# dc-dc_eth_pump.net
KiCad netlist of a schematic drawn in Altium Designer
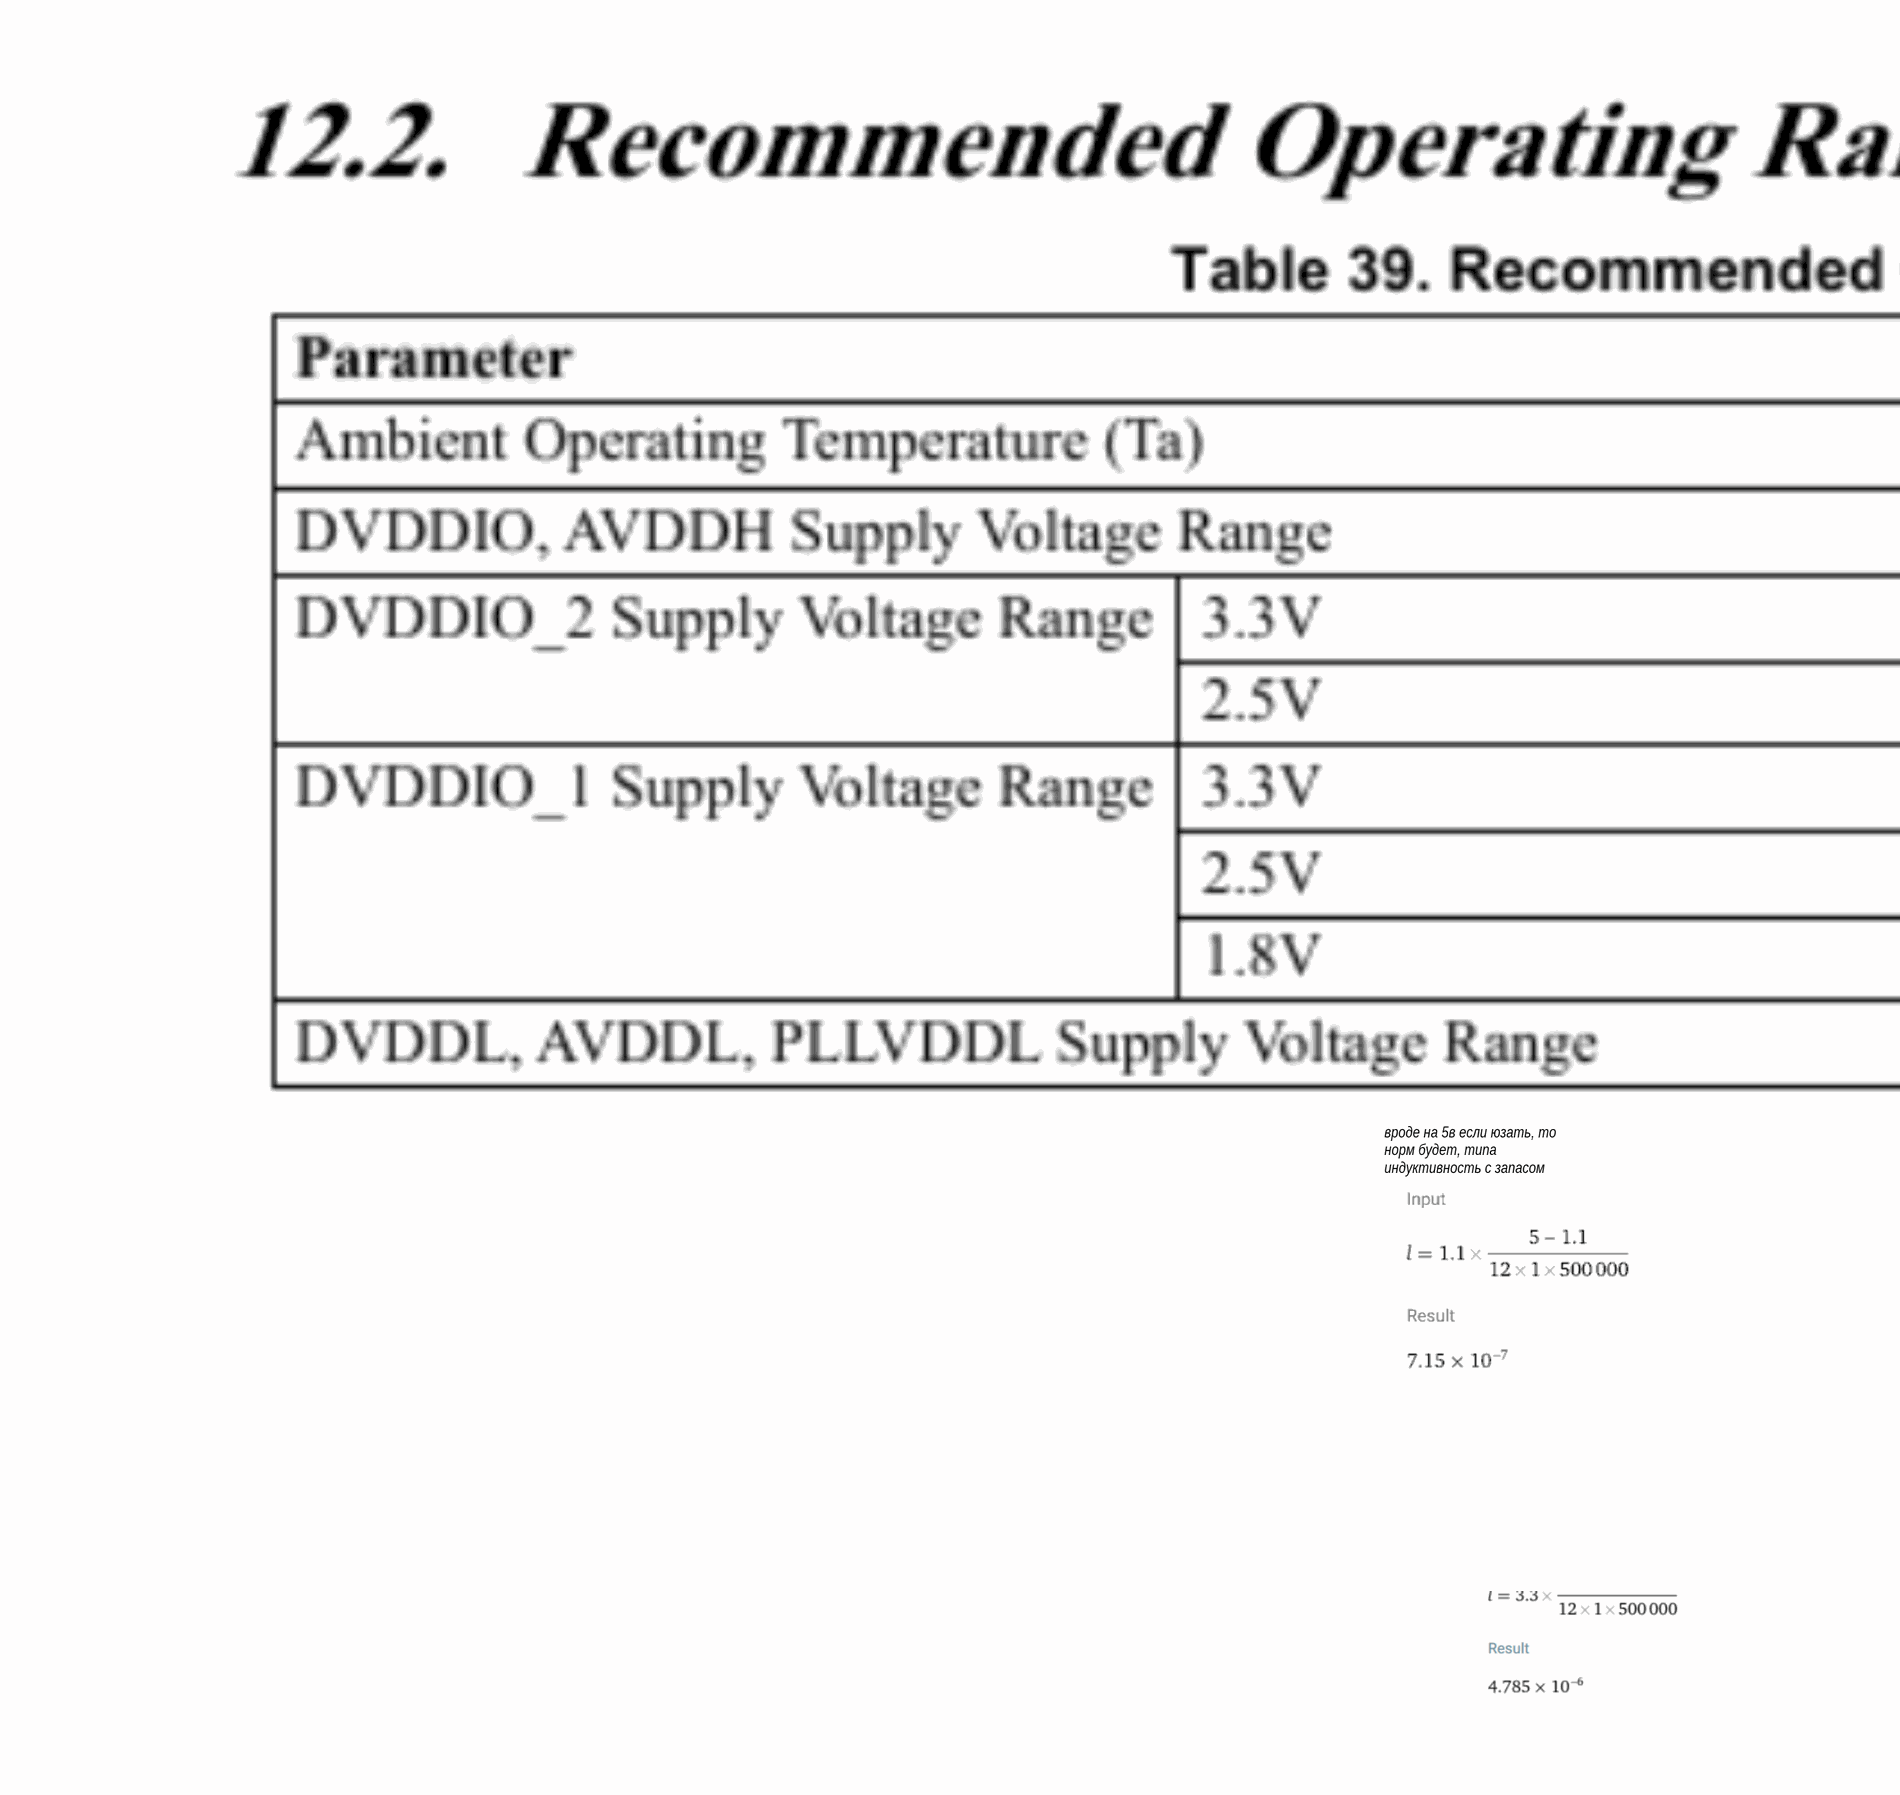
[diagram p0: dc-dc_eth+pump.SchDoc, top left]
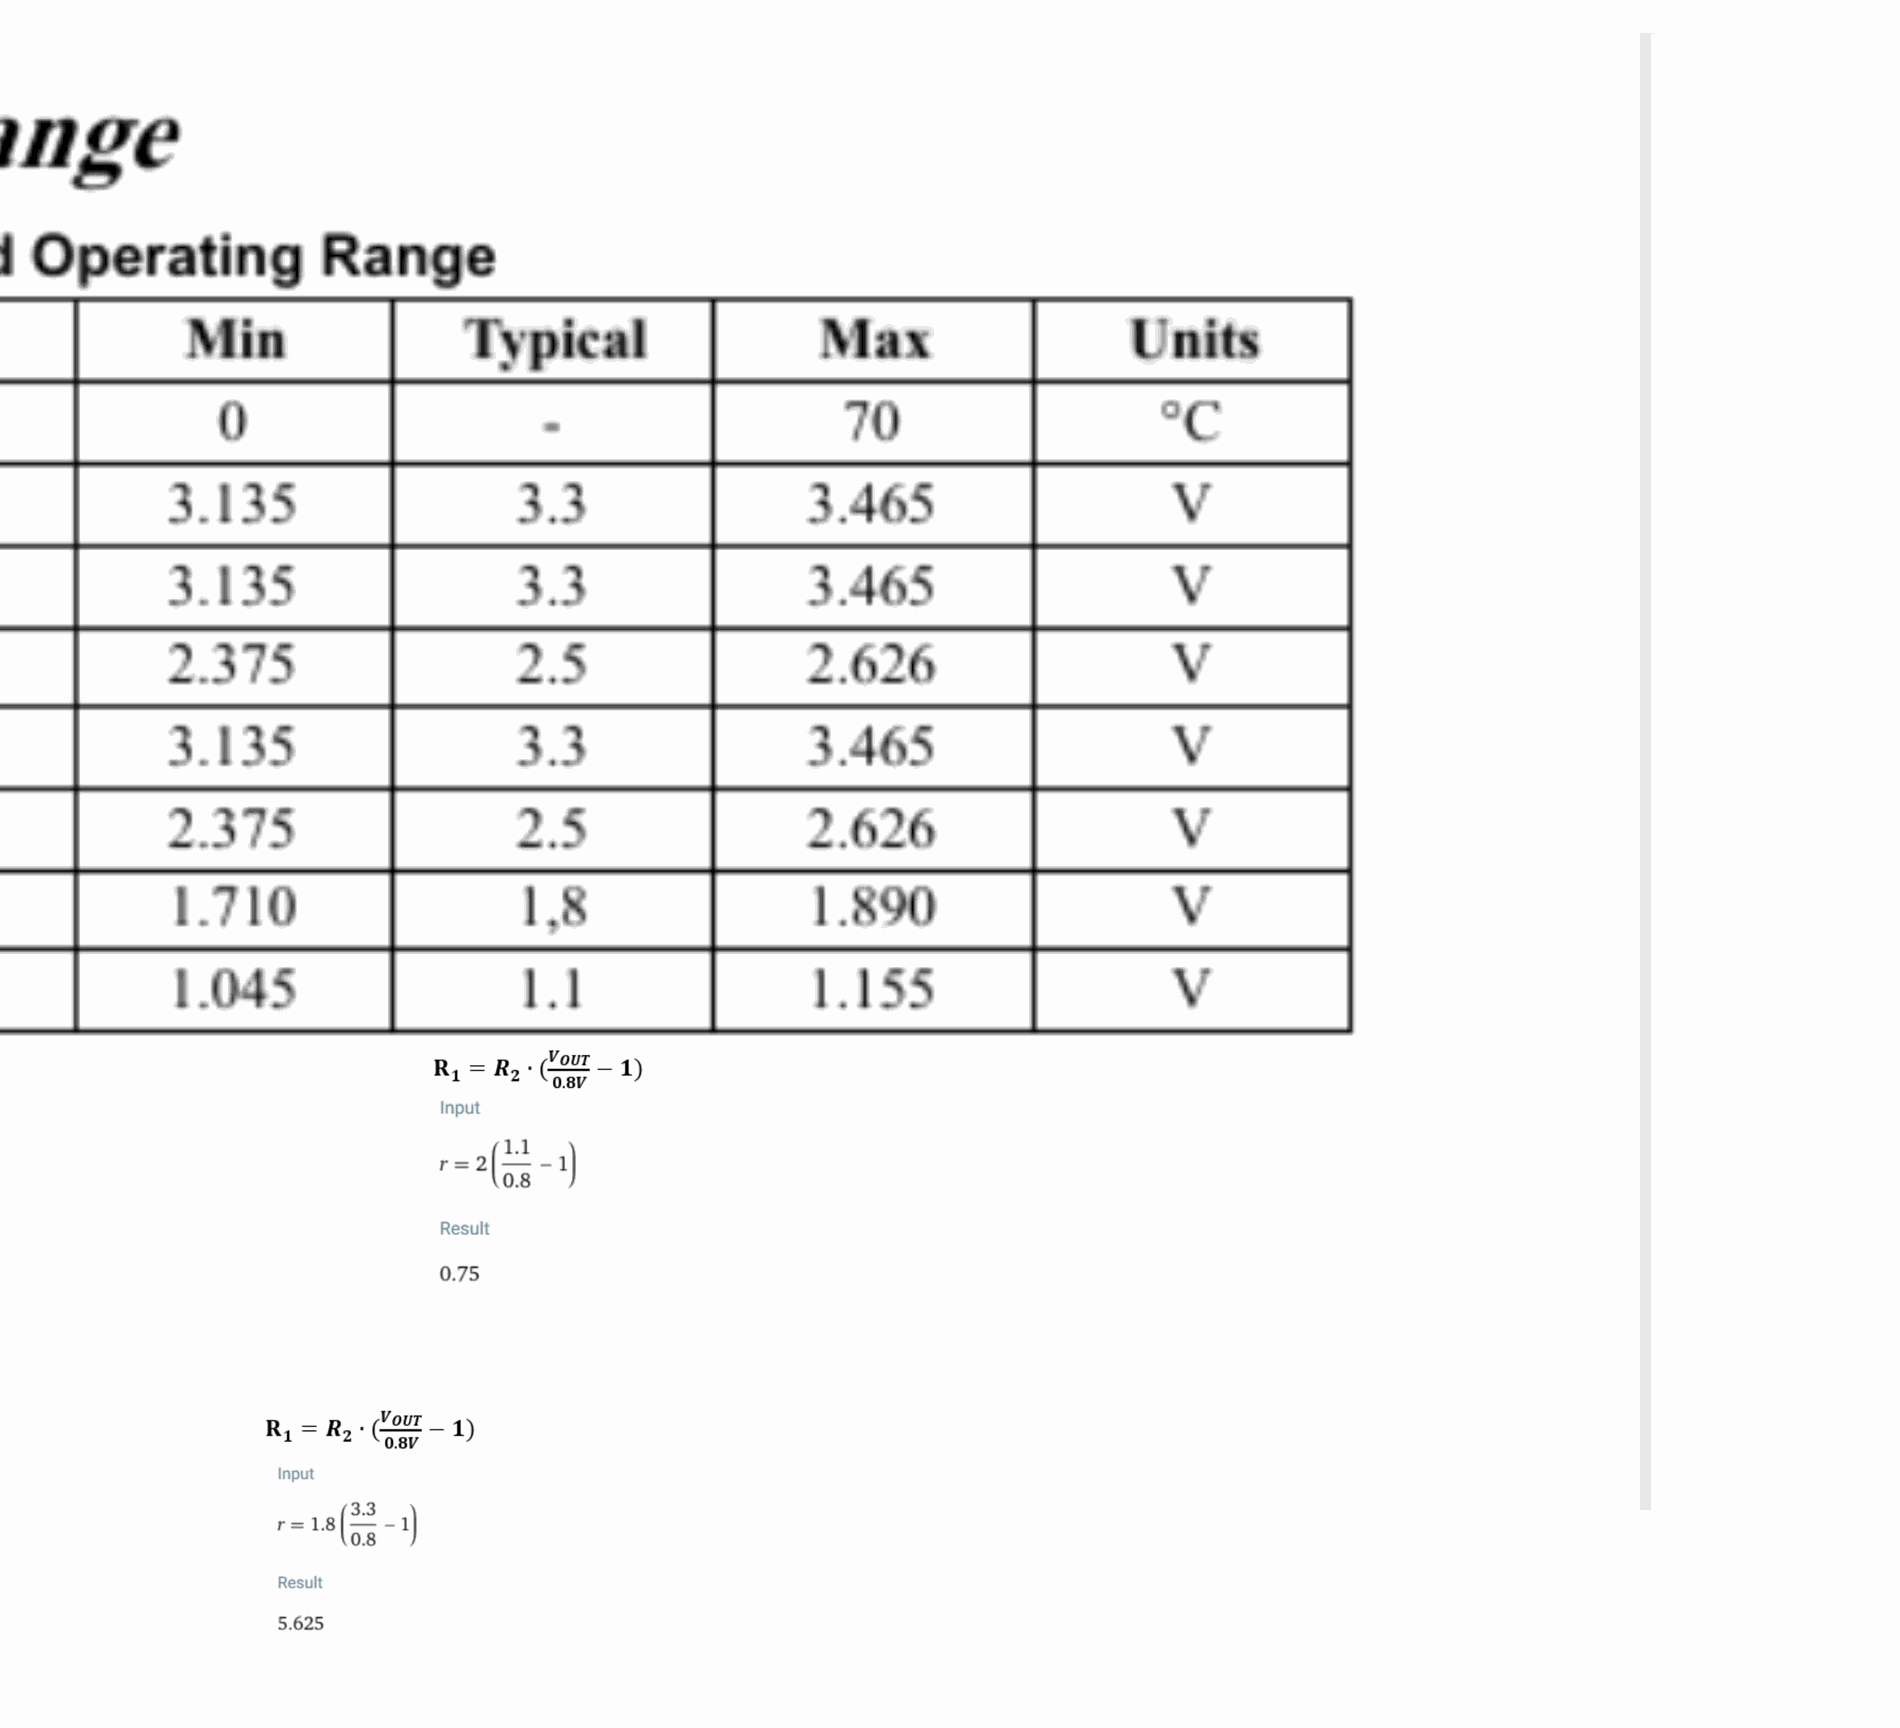
[diagram p1: dc-dc_eth+pump.SchDoc, top right]
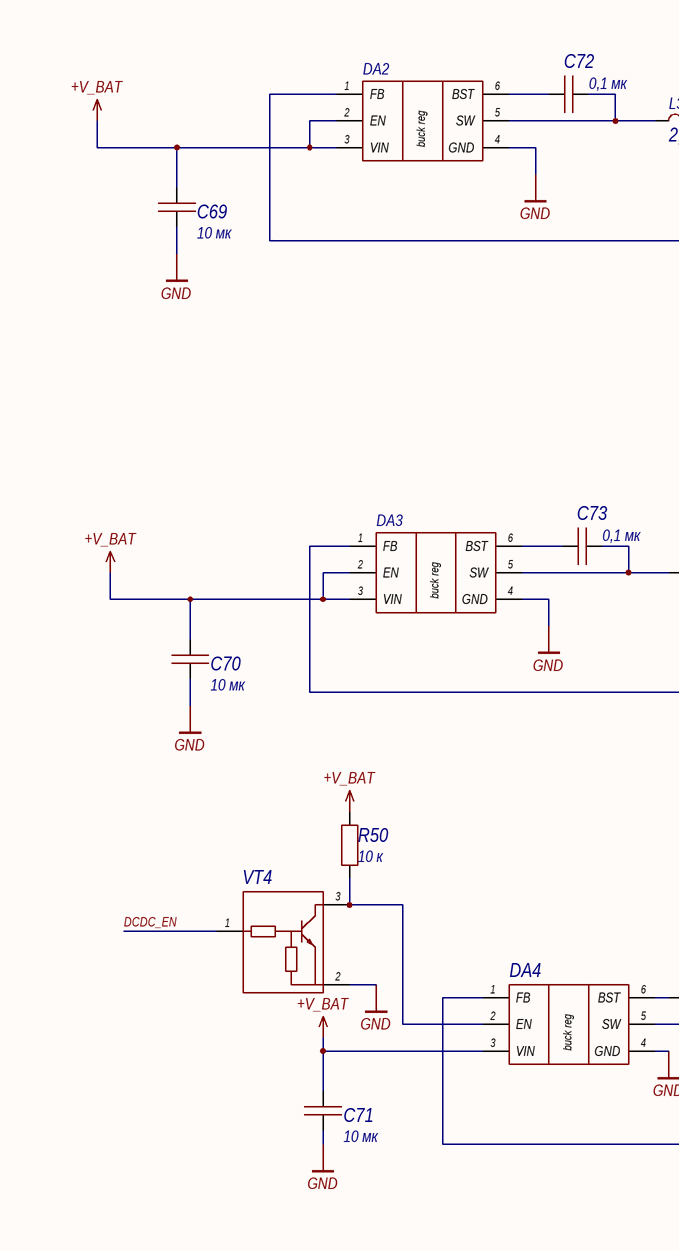
[diagram p2: dc-dc_eth+pump.SchDoc, bottom left]
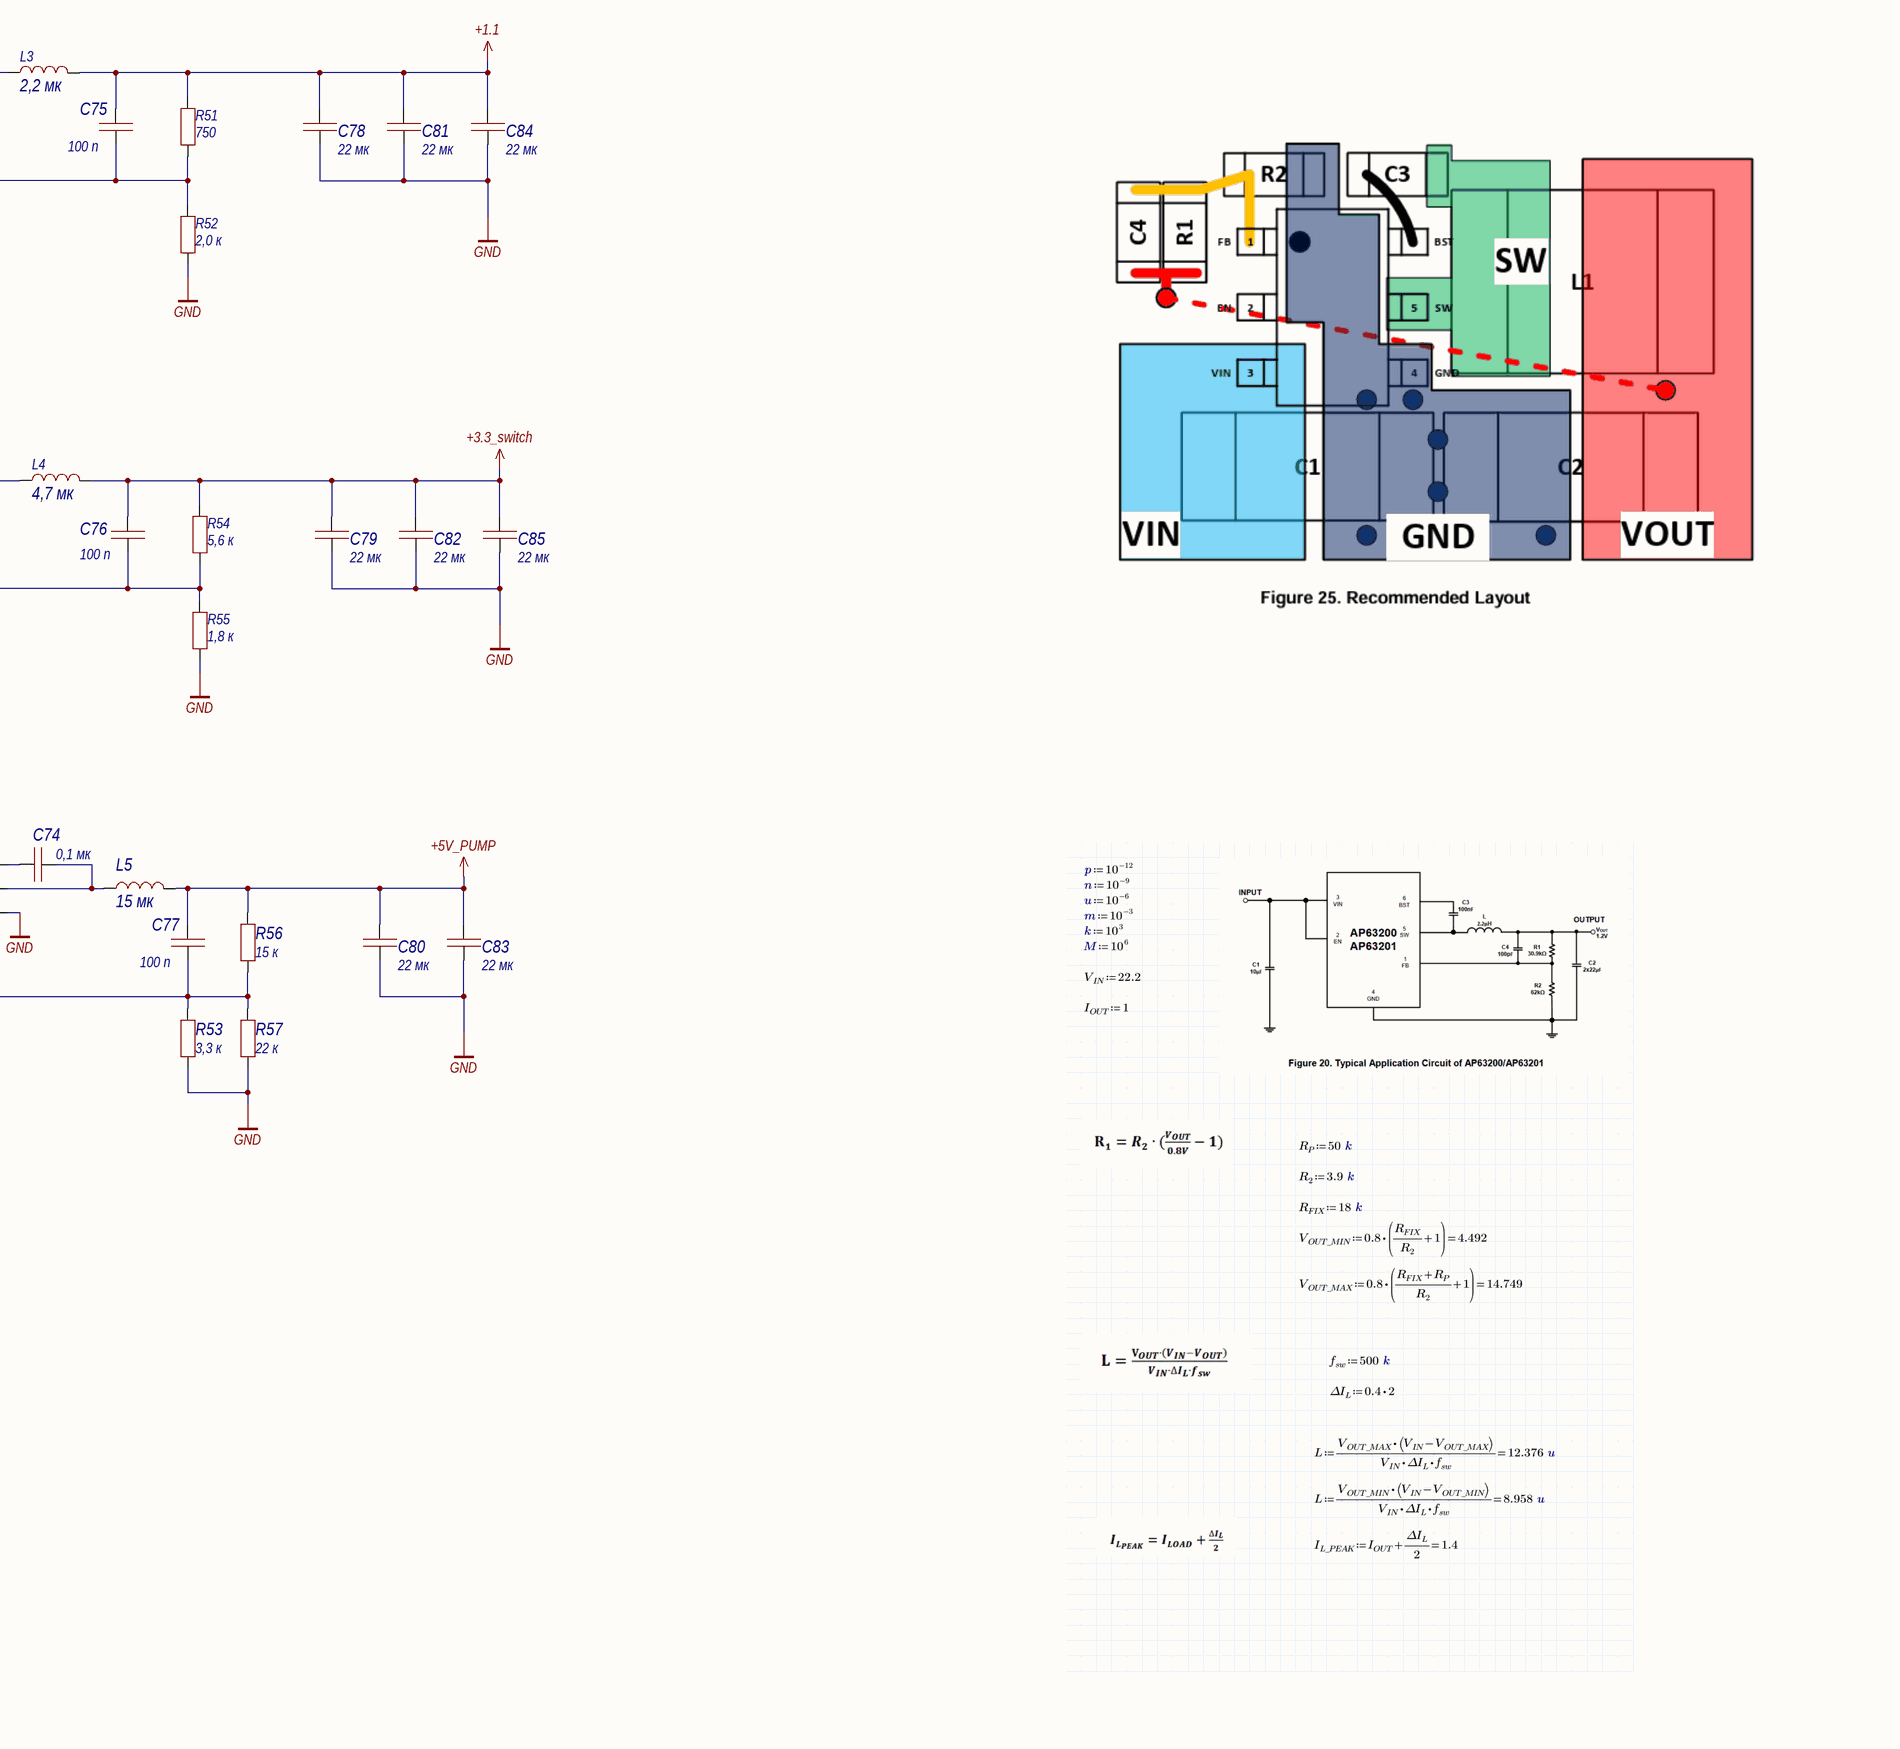
[diagram p3: dc-dc_eth+pump.SchDoc, bottom right]

(export (version "E")
  (design (tool "Eeschema 10.0.6"))
  (components
    (comp (ref "C69")
      (value "10 мк")
      (footprint "1210C")
      (description "Конденсатор 1210C ёмкостью 10 мк 10%, 35 В, X7R")
      (fields (field (name "PART NUMBER") "Capacitor_10u_10_35V_X7R_1210C") (field (name "TOLERANCE") "10%"))
      (libsource (lib "Hydrolib") (part "Capacitor"))
    )
    (comp (ref "C70")
      (value "10 мк")
      (footprint "1210C")
      (description "Конденсатор 1210C ёмкостью 10 мк 10%, 35 В, X7R")
      (fields (field (name "PART NUMBER") "Capacitor_10u_10_35V_X7R_1210C") (field (name "TOLERANCE") "10%"))
      (libsource (lib "Hydrolib") (part "Capacitor"))
    )
    (comp (ref "C71")
      (value "10 мк")
      (footprint "1210C")
      (description "Конденсатор 1210C ёмкостью 10 мк 10%, 35 В, X7R")
      (fields (field (name "PART NUMBER") "Capacitor_10u_10_35V_X7R_1210C") (field (name "TOLERANCE") "10%"))
      (libsource (lib "Hydrolib") (part "Capacitor"))
    )
    (comp (ref "C72")
      (value "0,1 мк")
      (footprint "0603C")
      (description "Конденсатор 0603C ёмкостью 0,1 мк 10%, 50 В, X7R")
      (fields (field (name "PART NUMBER") "Capacitor_0,1u_10_50V_X7R_0603C") (field (name "TOLERANCE") "10%"))
      (libsource (lib "Hydrolib") (part "Capacitor"))
    )
    (comp (ref "C73")
      (value "0,1 мк")
      (footprint "0603C")
      (description "Конденсатор 0603C ёмкостью 0,1 мк 10%, 50 В, X7R")
      (fields (field (name "PART NUMBER") "Capacitor_0,1u_10_50V_X7R_0603C") (field (name "TOLERANCE") "10%"))
      (libsource (lib "Hydrolib") (part "Capacitor"))
    )
    (comp (ref "C74")
      (value "0,1 мк")
      (footprint "0603C")
      (description "Конденсатор 0603C ёмкостью 0,1 мк 10%, 50 В, X7R")
      (fields (field (name "PART NUMBER") "Capacitor_0,1u_10_50V_X7R_0603C") (field (name "TOLERANCE") "10%"))
      (libsource (lib "Hydrolib") (part "Capacitor"))
    )
    (comp (ref "C75")
      (value "100 п")
      (footprint "0603C")
      (description "Конденсатор 0603C ёмкостью 100 п 10%, 50 В, X7R")
      (fields (field (name "PART NUMBER") "Capacitor_100p_10_50V_X7R_0603C") (field (name "TOLERANCE") "10%"))
      (libsource (lib "Hydrolib") (part "Capacitor"))
    )
    (comp (ref "C76")
      (value "100 п")
      (footprint "0603C")
      (description "Конденсатор 0603C ёмкостью 100 п 10%, 50 В, X7R")
      (fields (field (name "PART NUMBER") "Capacitor_100p_10_50V_X7R_0603C") (field (name "TOLERANCE") "10%"))
      (libsource (lib "Hydrolib") (part "Capacitor"))
    )
    (comp (ref "C77")
      (value "100 п")
      (footprint "0603C")
      (description "Конденсатор 0603C ёмкостью 100 п 10%, 50 В, X7R")
      (fields (field (name "PART NUMBER") "Capacitor_100p_10_50V_X7R_0603C") (field (name "TOLERANCE") "10%"))
      (libsource (lib "Hydrolib") (part "Capacitor"))
    )
    (comp (ref "C78")
      (value "22 мк")
      (footprint "1210C")
      (description "Конденсатор 1210C ёмкостью 22 мк 10%, 25 В, X7R")
      (fields (field (name "PART NUMBER") "Capacitor_22u_10_25V_X7R_1210C") (field (name "TOLERANCE") "10%"))
      (libsource (lib "Hydrolib") (part "Capacitor"))
    )
    (comp (ref "C79")
      (value "22 мк")
      (footprint "1210C")
      (description "Конденсатор 1210C ёмкостью 22 мк 10%, 25 В, X7R")
      (fields (field (name "PART NUMBER") "Capacitor_22u_10_25V_X7R_1210C") (field (name "TOLERANCE") "10%"))
      (libsource (lib "Hydrolib") (part "Capacitor"))
    )
    (comp (ref "C80")
      (value "22 мк")
      (footprint "1210C")
      (description "Конденсатор 1210C ёмкостью 22 мк 10%, 25 В, X7R")
      (fields (field (name "PART NUMBER") "Capacitor_22u_10_25V_X7R_1210C") (field (name "TOLERANCE") "10%"))
      (libsource (lib "Hydrolib") (part "Capacitor"))
    )
    (comp (ref "C81")
      (value "22 мк")
      (footprint "1210C")
      (description "Конденсатор 1210C ёмкостью 22 мк 10%, 25 В, X7R")
      (fields (field (name "PART NUMBER") "Capacitor_22u_10_25V_X7R_1210C") (field (name "TOLERANCE") "10%"))
      (libsource (lib "Hydrolib") (part "Capacitor"))
    )
    (comp (ref "C82")
      (value "22 мк")
      (footprint "1210C")
      (description "Конденсатор 1210C ёмкостью 22 мк 10%, 25 В, X7R")
      (fields (field (name "PART NUMBER") "Capacitor_22u_10_25V_X7R_1210C") (field (name "TOLERANCE") "10%"))
      (libsource (lib "Hydrolib") (part "Capacitor"))
    )
    (comp (ref "C83")
      (value "22 мк")
      (footprint "1210C")
      (description "Конденсатор 1210C ёмкостью 22 мк 10%, 25 В, X7R")
      (fields (field (name "PART NUMBER") "Capacitor_22u_10_25V_X7R_1210C") (field (name "TOLERANCE") "10%"))
      (libsource (lib "Hydrolib") (part "Capacitor"))
    )
    (comp (ref "C84")
      (value "22 мк")
      (footprint "1210C")
      (description "Конденсатор 1210C ёмкостью 22 мк 10%, 25 В, X7R")
      (fields (field (name "PART NUMBER") "Capacitor_22u_10_25V_X7R_1210C") (field (name "TOLERANCE") "10%"))
      (libsource (lib "Hydrolib") (part "Capacitor"))
    )
    (comp (ref "C85")
      (value "22 мк")
      (footprint "1210C")
      (description "Конденсатор 1210C ёмкостью 22 мк 10%, 25 В, X7R")
      (fields (field (name "PART NUMBER") "Capacitor_22u_10_25V_X7R_1210C") (field (name "TOLERANCE") "10%"))
      (libsource (lib "Hydrolib") (part "Capacitor"))
    )
    (comp (ref "DA2")
      (value "AP63200")
      (footprint "TSOT26")
      (description "DC-DC понижающий преобразователь, Vin: 3.8 - 40 В, adj, 2 А")
      (libsource (lib "Hydrolib") (part "AP63200"))
    )
    (comp (ref "DA3")
      (value "AP63200")
      (footprint "TSOT26")
      (description "DC-DC понижающий преобразователь, Vin: 3.8 - 40 В, adj, 2 А")
      (libsource (lib "Hydrolib") (part "AP63200"))
    )
    (comp (ref "DA4")
      (value "AP63200")
      (footprint "TSOT26")
      (description "DC-DC понижающий преобразователь, Vin: 3.8 - 40 В, adj, 2 А")
      (libsource (lib "Hydrolib") (part "AP63200"))
    )
    (comp (ref "L3")
      (value "2,2 мк")
      (footprint "CDRH6D12")
      (description "Индуктивность на 2,2 мкГн, номинальный ток 2,5 А")
      (fields (field (name "PART NUMBER") "CDRH6D12NP-2R2NC") (field (name "АВТОР") "rreali"))
      (libsource (lib "Hydrolib") (part "Inductance_1-3"))
    )
    (comp (ref "L4")
      (value "4,7 мк")
      (footprint "B82462G4")
      (description "Индуктивность на 4,7 мкГн, номинальный ток 2,5 А")
      (fields (field (name "PART NUMBER") "B82472G6472M") (field (name "АВТОР") "rreali"))
      (libsource (lib "Hydrolib") (part "Inductance"))
    )
    (comp (ref "L5")
      (value "15 мк")
      (footprint "SP43")
      (description "Индуктивность на 15 мкГн, номинальный ток 1,3 А")
      (fields (field (name "PART NUMBER") "SP43-150K"))
      (libsource (lib "Hydrolib") (part "Inductance"))
    )
    (comp (ref "R50")
      (value "10 к")
      (footprint "0603R")
      (description "Резистор номиналом 10 кОм 1%")
      (fields (field (name "PART NUMBER") "Resistor_10k_1_0603") (field (name "TOLERANCE") "1%"))
      (libsource (lib "Hydrolib") (part "Resistor"))
    )
    (comp (ref "R51")
      (value "750")
      (footprint "0603R")
      (description "Резистор номиналом 750 Ом 1%")
      (fields (field (name "PART NUMBER") "Resistor_750_1_0603") (field (name "TOLERANCE") "1%"))
      (libsource (lib "Hydrolib") (part "Resistor"))
    )
    (comp (ref "R52")
      (value "2,0 к")
      (footprint "0603R")
      (description "Резистор номиналом 2,0 кОм 1%")
      (fields (field (name "PART NUMBER") "Resistor_2.0k_1_0603") (field (name "TOLERANCE") "1%"))
      (libsource (lib "Hydrolib") (part "Resistor"))
    )
    (comp (ref "R53")
      (value "3,3 к")
      (footprint "0603R")
      (description "Резистор номиналом 3,3 кОм 1%")
      (fields (field (name "PART NUMBER") "Resistor_3.3k_1_0603") (field (name "TOLERANCE") "1%"))
      (libsource (lib "Hydrolib") (part "Resistor"))
    )
    (comp (ref "R54")
      (value "5,6 к")
      (footprint "0603R")
      (description "Резистор номиналом 5,6 кОм 1%")
      (fields (field (name "PART NUMBER") "Resistor_5.6k_1_0603") (field (name "TOLERANCE") "1%"))
      (libsource (lib "Hydrolib") (part "Resistor"))
    )
    (comp (ref "R55")
      (value "1,8 к")
      (footprint "0603R")
      (description "Резистор номиналом 1,8 кОм 1%")
      (fields (field (name "PART NUMBER") "Resistor_1.8k_1_0603") (field (name "TOLERANCE") "1%"))
      (libsource (lib "Hydrolib") (part "Resistor"))
    )
    (comp (ref "R56")
      (value "15 к")
      (footprint "0603R")
      (description "Резистор номиналом 15 кОм 1%")
      (fields (field (name "PART NUMBER") "Resistor_15k_1_0603") (field (name "TOLERANCE") "1%"))
      (libsource (lib "Hydrolib") (part "Resistor"))
    )
    (comp (ref "R57")
      (value "22 к")
      (footprint "0603R")
      (description "Резистор номиналом 22 кОм 1%")
      (fields (field (name "PART NUMBER") "Resistor_22k_1_0603") (field (name "TOLERANCE") "1%"))
      (libsource (lib "Hydrolib") (part "Resistor"))
    )
    (comp (ref "VT4")
      (value "PDTC114ET")
      (footprint "SOT23-3")
      (description "цифровой npn 50в 100мА")
      (libsource (lib "Hydrolib") (part "PDTC114ET"))
    )
  )
  (nets
    (net (code "1") (name "+1.1") (class "Default")
      (node (ref "C75") (pin "2") (pinfunction "2_2") (pintype "passive"))
      (node (ref "C78") (pin "2") (pinfunction "2_2") (pintype "passive"))
      (node (ref "C81") (pin "2") (pinfunction "2_2") (pintype "passive"))
      (node (ref "C84") (pin "2") (pinfunction "2_2") (pintype "passive"))
      (node (ref "L3") (pin "3") (pinfunction "3_3") (pintype "passive"))
      (node (ref "R51") (pin "2") (pinfunction "2_2") (pintype "passive"))
    )
    (net (code "2") (name "+3.3_switch") (class "Default")
      (node (ref "C76") (pin "2") (pinfunction "2_2") (pintype "passive"))
      (node (ref "C79") (pin "2") (pinfunction "2_2") (pintype "passive"))
      (node (ref "C82") (pin "2") (pinfunction "2_2") (pintype "passive"))
      (node (ref "C85") (pin "2") (pinfunction "2_2") (pintype "passive"))
      (node (ref "L4") (pin "2") (pinfunction "2_2") (pintype "passive"))
      (node (ref "R54") (pin "2") (pinfunction "2_2") (pintype "passive"))
    )
    (net (code "3") (name "+5V_PUMP") (class "Default")
      (node (ref "C77") (pin "2") (pinfunction "2_2") (pintype "passive"))
      (node (ref "C80") (pin "2") (pinfunction "2_2") (pintype "passive"))
      (node (ref "C83") (pin "2") (pinfunction "2_2") (pintype "passive"))
      (node (ref "L5") (pin "2") (pinfunction "2_2") (pintype "passive"))
      (node (ref "R56") (pin "2") (pinfunction "2_2") (pintype "passive"))
    )
    (net (code "4") (name "+V_BAT") (class "Default")
      (node (ref "C69") (pin "2") (pinfunction "2_2") (pintype "passive"))
      (node (ref "C70") (pin "2") (pinfunction "2_2") (pintype "passive"))
      (node (ref "C71") (pin "2") (pinfunction "2_2") (pintype "passive"))
      (node (ref "DA2") (pin "2") (pinfunction "EN_2") (pintype "passive"))
      (node (ref "DA2") (pin "3") (pinfunction "VIN_3") (pintype "passive"))
      (node (ref "DA3") (pin "2") (pinfunction "EN_2") (pintype "passive"))
      (node (ref "DA3") (pin "3") (pinfunction "VIN_3") (pintype "passive"))
      (node (ref "DA4") (pin "3") (pinfunction "VIN_3") (pintype "passive"))
      (node (ref "R50") (pin "2") (pinfunction "2_2") (pintype "passive"))
    )
    (net (code "5") (name "/DCDC_EN") (class "Default")
      (node (ref "VT4") (pin "1") (pinfunction "B_1") (pintype "passive"))
    )
    (net (code "6") (name "GND") (class "Default")
      (node (ref "C69") (pin "1") (pinfunction "1_1") (pintype "passive"))
      (node (ref "C70") (pin "1") (pinfunction "1_1") (pintype "passive"))
      (node (ref "C71") (pin "1") (pinfunction "1_1") (pintype "passive"))
      (node (ref "C78") (pin "1") (pinfunction "1_1") (pintype "passive"))
      (node (ref "C79") (pin "1") (pinfunction "1_1") (pintype "passive"))
      (node (ref "C80") (pin "1") (pinfunction "1_1") (pintype "passive"))
      (node (ref "C81") (pin "1") (pinfunction "1_1") (pintype "passive"))
      (node (ref "C82") (pin "1") (pinfunction "1_1") (pintype "passive"))
      (node (ref "C83") (pin "1") (pinfunction "1_1") (pintype "passive"))
      (node (ref "C84") (pin "1") (pinfunction "1_1") (pintype "passive"))
      (node (ref "C85") (pin "1") (pinfunction "1_1") (pintype "passive"))
      (node (ref "DA2") (pin "4") (pinfunction "GND_4") (pintype "passive"))
      (node (ref "DA3") (pin "4") (pinfunction "GND_4") (pintype "passive"))
      (node (ref "DA4") (pin "4") (pinfunction "GND_4") (pintype "passive"))
      (node (ref "R52") (pin "1") (pinfunction "1_1") (pintype "passive"))
      (node (ref "R53") (pin "1") (pinfunction "1_1") (pintype "passive"))
      (node (ref "R55") (pin "1") (pinfunction "1_1") (pintype "passive"))
      (node (ref "R57") (pin "1") (pinfunction "1_1") (pintype "passive"))
      (node (ref "VT4") (pin "2") (pinfunction "E_2") (pintype "passive"))
    )
    (net (code "7") (name "Net-(DA2-BST)") (class "Default")
      (node (ref "C72") (pin "1") (pinfunction "1_1") (pintype "passive"))
      (node (ref "DA2") (pin "6") (pinfunction "BST_6") (pintype "passive"))
    )
    (net (code "8") (name "Net-(DA2-FB)") (class "Default")
      (node (ref "C75") (pin "1") (pinfunction "1_1") (pintype "passive"))
      (node (ref "DA2") (pin "1") (pinfunction "FB_1") (pintype "passive"))
      (node (ref "R51") (pin "1") (pinfunction "1_1") (pintype "passive"))
      (node (ref "R52") (pin "2") (pinfunction "2_2") (pintype "passive"))
    )
    (net (code "9") (name "Net-(DA2-SW)") (class "Default")
      (node (ref "C72") (pin "2") (pinfunction "2_2") (pintype "passive"))
      (node (ref "DA2") (pin "5") (pinfunction "SW_5") (pintype "passive"))
      (node (ref "L3") (pin "1") (pinfunction "1_1") (pintype "passive"))
    )
    (net (code "10") (name "Net-(DA3-BST)") (class "Default")
      (node (ref "C73") (pin "1") (pinfunction "1_1") (pintype "passive"))
      (node (ref "DA3") (pin "6") (pinfunction "BST_6") (pintype "passive"))
    )
    (net (code "11") (name "Net-(DA3-FB)") (class "Default")
      (node (ref "C76") (pin "1") (pinfunction "1_1") (pintype "passive"))
      (node (ref "DA3") (pin "1") (pinfunction "FB_1") (pintype "passive"))
      (node (ref "R54") (pin "1") (pinfunction "1_1") (pintype "passive"))
      (node (ref "R55") (pin "2") (pinfunction "2_2") (pintype "passive"))
    )
    (net (code "12") (name "Net-(DA3-SW)") (class "Default")
      (node (ref "C73") (pin "2") (pinfunction "2_2") (pintype "passive"))
      (node (ref "DA3") (pin "5") (pinfunction "SW_5") (pintype "passive"))
      (node (ref "L4") (pin "1") (pinfunction "1_1") (pintype "passive"))
    )
    (net (code "13") (name "Net-(DA4-BST)") (class "Default")
      (node (ref "C74") (pin "1") (pinfunction "1_1") (pintype "passive"))
      (node (ref "DA4") (pin "6") (pinfunction "BST_6") (pintype "passive"))
    )
    (net (code "14") (name "Net-(DA4-EN)") (class "Default")
      (node (ref "DA4") (pin "2") (pinfunction "EN_2") (pintype "passive"))
      (node (ref "R50") (pin "1") (pinfunction "1_1") (pintype "passive"))
      (node (ref "VT4") (pin "3") (pinfunction "C_3") (pintype "passive"))
    )
    (net (code "15") (name "Net-(DA4-FB)") (class "Default")
      (node (ref "C77") (pin "1") (pinfunction "1_1") (pintype "passive"))
      (node (ref "DA4") (pin "1") (pinfunction "FB_1") (pintype "passive"))
      (node (ref "R53") (pin "2") (pinfunction "2_2") (pintype "passive"))
      (node (ref "R56") (pin "1") (pinfunction "1_1") (pintype "passive"))
      (node (ref "R57") (pin "2") (pinfunction "2_2") (pintype "passive"))
    )
    (net (code "16") (name "Net-(DA4-SW)") (class "Default")
      (node (ref "C74") (pin "2") (pinfunction "2_2") (pintype "passive"))
      (node (ref "DA4") (pin "5") (pinfunction "SW_5") (pintype "passive"))
      (node (ref "L5") (pin "1") (pinfunction "1_1") (pintype "passive"))
    )
  )
)
